# WarningPanel.net
KiCad netlist of a schematic drawn in EAGLE
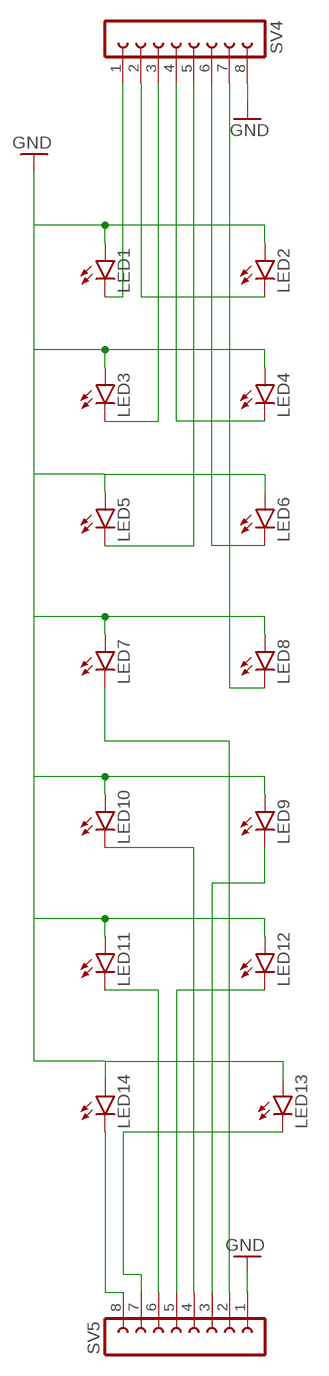
[diagram p0: schematic, sheet 1]

(export (version "E")
  (design (tool "Eeschema 10.0.6"))
  (components
    (comp (ref "LED1")
      (value "LED5MM")
      (footprint "eagle-import:LED5MM")
      (libsource (lib "eagle-import") (part "LED5MM"))
    )
    (comp (ref "LED2")
      (value "LED5MM")
      (footprint "eagle-import:LED5MM")
      (libsource (lib "eagle-import") (part "LED5MM"))
    )
    (comp (ref "LED3")
      (value "LED5MM")
      (footprint "eagle-import:LED5MM")
      (libsource (lib "eagle-import") (part "LED5MM"))
    )
    (comp (ref "LED4")
      (value "LED5MM")
      (footprint "eagle-import:LED5MM")
      (libsource (lib "eagle-import") (part "LED5MM"))
    )
    (comp (ref "LED5")
      (value "LED5MM")
      (footprint "eagle-import:LED5MM")
      (libsource (lib "eagle-import") (part "LED5MM"))
    )
    (comp (ref "LED6")
      (value "LED5MM")
      (footprint "eagle-import:LED5MM")
      (libsource (lib "eagle-import") (part "LED5MM"))
    )
    (comp (ref "LED7")
      (value "LED5MM")
      (footprint "eagle-import:LED5MM")
      (libsource (lib "eagle-import") (part "LED5MM"))
    )
    (comp (ref "LED8")
      (value "LED5MM")
      (footprint "eagle-import:LED5MM")
      (libsource (lib "eagle-import") (part "LED5MM"))
    )
    (comp (ref "LED9")
      (value "LED5MM")
      (footprint "eagle-import:LED5MM")
      (libsource (lib "eagle-import") (part "LED5MM"))
    )
    (comp (ref "LED10")
      (value "LED5MM")
      (footprint "eagle-import:LED5MM")
      (libsource (lib "eagle-import") (part "LED5MM"))
    )
    (comp (ref "LED11")
      (value "LED5MM")
      (footprint "eagle-import:LED5MM")
      (libsource (lib "eagle-import") (part "LED5MM"))
    )
    (comp (ref "LED12")
      (value "LED5MM")
      (footprint "eagle-import:LED5MM")
      (libsource (lib "eagle-import") (part "LED5MM"))
    )
    (comp (ref "LED13")
      (value "LED5MM")
      (footprint "eagle-import:LED5MM")
      (libsource (lib "eagle-import") (part "LED5MM"))
    )
    (comp (ref "LED14")
      (value "LED5MM")
      (footprint "eagle-import:LED5MM")
      (libsource (lib "eagle-import") (part "LED5MM"))
    )
    (comp (ref "SV4")
      (value "FE08-1")
      (footprint "eagle-import:FE08")
      (libsource (lib "eagle-import") (part "FE08-1"))
    )
    (comp (ref "SV5")
      (value "FE08-1")
      (footprint "eagle-import:FE08")
      (libsource (lib "eagle-import") (part "FE08-1"))
    )
  )
  (nets
    (net (code "1") (name "GND") (class "Default")
      (node (ref "LED13") (pin "A") (pinfunction "A_A") (pintype "passive"))
      (node (ref "LED14") (pin "A") (pinfunction "A_A") (pintype "passive"))
      (node (ref "SV4") (pin "8") (pinfunction "8_8") (pintype "passive"))
      (node (ref "SV5") (pin "1") (pinfunction "1_1") (pintype "passive"))
    )
    (net (code "2") (name "Net-(LED1-C)") (class "Default")
      (node (ref "LED1") (pin "K") (pinfunction "C_K") (pintype "passive"))
      (node (ref "SV4") (pin "1") (pinfunction "1_1") (pintype "passive"))
    )
    (net (code "3") (name "Net-(LED1-PadA)") (class "Default")
      (node (ref "LED1") (pin "A") (pinfunction "A_A") (pintype "passive"))
      (node (ref "LED2") (pin "A") (pinfunction "A_A") (pintype "passive"))
    )
    (net (code "4") (name "Net-(LED2-C)") (class "Default")
      (node (ref "LED2") (pin "K") (pinfunction "C_K") (pintype "passive"))
      (node (ref "SV4") (pin "2") (pinfunction "2_2") (pintype "passive"))
    )
    (net (code "5") (name "Net-(LED3-C)") (class "Default")
      (node (ref "LED3") (pin "K") (pinfunction "C_K") (pintype "passive"))
      (node (ref "SV4") (pin "3") (pinfunction "3_3") (pintype "passive"))
    )
    (net (code "6") (name "Net-(LED3-PadA)") (class "Default")
      (node (ref "LED3") (pin "A") (pinfunction "A_A") (pintype "passive"))
      (node (ref "LED4") (pin "A") (pinfunction "A_A") (pintype "passive"))
    )
    (net (code "7") (name "Net-(LED4-C)") (class "Default")
      (node (ref "LED4") (pin "K") (pinfunction "C_K") (pintype "passive"))
      (node (ref "SV4") (pin "4") (pinfunction "4_4") (pintype "passive"))
    )
    (net (code "8") (name "Net-(LED5-C)") (class "Default")
      (node (ref "LED5") (pin "K") (pinfunction "C_K") (pintype "passive"))
      (node (ref "SV4") (pin "5") (pinfunction "5_5") (pintype "passive"))
    )
    (net (code "9") (name "Net-(LED5-PadA)") (class "Default")
      (node (ref "LED5") (pin "A") (pinfunction "A_A") (pintype "passive"))
      (node (ref "LED6") (pin "A") (pinfunction "A_A") (pintype "passive"))
    )
    (net (code "10") (name "Net-(LED6-C)") (class "Default")
      (node (ref "LED6") (pin "K") (pinfunction "C_K") (pintype "passive"))
      (node (ref "SV4") (pin "6") (pinfunction "6_6") (pintype "passive"))
    )
    (net (code "11") (name "Net-(LED7-C)") (class "Default")
      (node (ref "LED7") (pin "K") (pinfunction "C_K") (pintype "passive"))
      (node (ref "SV5") (pin "2") (pinfunction "2_2") (pintype "passive"))
    )
    (net (code "12") (name "Net-(LED7-PadA)") (class "Default")
      (node (ref "LED7") (pin "A") (pinfunction "A_A") (pintype "passive"))
      (node (ref "LED8") (pin "A") (pinfunction "A_A") (pintype "passive"))
    )
    (net (code "13") (name "Net-(LED8-C)") (class "Default")
      (node (ref "LED8") (pin "K") (pinfunction "C_K") (pintype "passive"))
      (node (ref "SV4") (pin "7") (pinfunction "7_7") (pintype "passive"))
    )
    (net (code "14") (name "Net-(LED9-C)") (class "Default")
      (node (ref "LED9") (pin "K") (pinfunction "C_K") (pintype "passive"))
      (node (ref "SV5") (pin "3") (pinfunction "3_3") (pintype "passive"))
    )
    (net (code "15") (name "Net-(LED10-C)") (class "Default")
      (node (ref "LED10") (pin "K") (pinfunction "C_K") (pintype "passive"))
      (node (ref "SV5") (pin "4") (pinfunction "4_4") (pintype "passive"))
    )
    (net (code "16") (name "Net-(LED10-PadA)") (class "Default")
      (node (ref "LED10") (pin "A") (pinfunction "A_A") (pintype "passive"))
      (node (ref "LED9") (pin "A") (pinfunction "A_A") (pintype "passive"))
    )
    (net (code "17") (name "Net-(LED11-C)") (class "Default")
      (node (ref "LED11") (pin "K") (pinfunction "C_K") (pintype "passive"))
      (node (ref "SV5") (pin "6") (pinfunction "6_6") (pintype "passive"))
    )
    (net (code "18") (name "Net-(LED11-PadA)") (class "Default")
      (node (ref "LED11") (pin "A") (pinfunction "A_A") (pintype "passive"))
      (node (ref "LED12") (pin "A") (pinfunction "A_A") (pintype "passive"))
    )
    (net (code "19") (name "Net-(LED12-C)") (class "Default")
      (node (ref "LED12") (pin "K") (pinfunction "C_K") (pintype "passive"))
      (node (ref "SV5") (pin "5") (pinfunction "5_5") (pintype "passive"))
    )
    (net (code "20") (name "Net-(LED13-C)") (class "Default")
      (node (ref "LED13") (pin "K") (pinfunction "C_K") (pintype "passive"))
      (node (ref "SV5") (pin "7") (pinfunction "7_7") (pintype "passive"))
    )
    (net (code "21") (name "Net-(LED14-C)") (class "Default")
      (node (ref "LED14") (pin "K") (pinfunction "C_K") (pintype "passive"))
      (node (ref "SV5") (pin "8") (pinfunction "8_8") (pintype "passive"))
    )
  )
)
